# rpihat.net
KiCad netlist of a schematic drawn in EAGLE
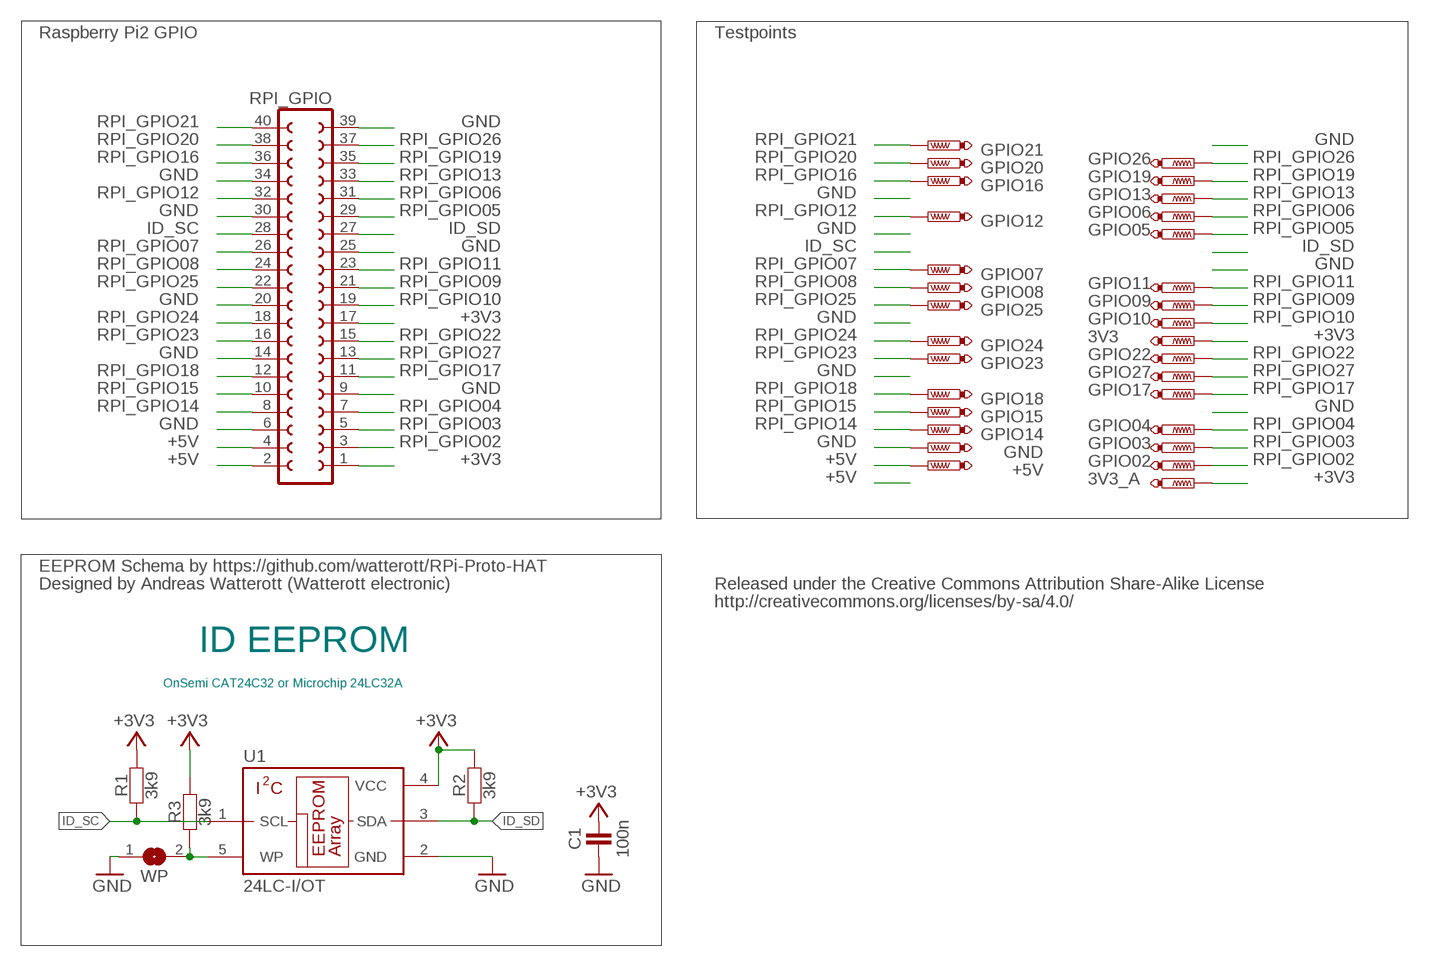
[diagram p0: schematic, sheet 1]

(export (version "E")
  (design (tool "Eeschema 10.0.6"))
  (components
    (comp (ref "+5V")
      (value "PTR1TP06R")
      (footprint "eagle-import:TP06R")
      (libsource (lib "eagle-import") (part "PTR1TP06R"))
    )
    (comp (ref "3V3")
      (value "+3.3V")
      (footprint "eagle-import:TP06R")
      (libsource (lib "eagle-import") (part "PTR1TP06R"))
    )
    (comp (ref "3V3_A")
      (value "+3.3V")
      (footprint "eagle-import:TP06R")
      (libsource (lib "eagle-import") (part "PTR1TP06R"))
    )
    (comp (ref "C1")
      (value "100n")
      (footprint "eagle-import:R0603")
      (libsource (lib "eagle-import") (part "CAPACITOR-C0603"))
    )
    (comp (ref "GND")
      (value "PTR1TP06R")
      (footprint "eagle-import:TP06R")
      (libsource (lib "eagle-import") (part "PTR1TP06R"))
    )
    (comp (ref "GPIO02")
      (value "PTR1TP06R")
      (footprint "eagle-import:TP06R")
      (libsource (lib "eagle-import") (part "PTR1TP06R"))
    )
    (comp (ref "GPIO03")
      (value "PTR1TP06R")
      (footprint "eagle-import:TP06R")
      (libsource (lib "eagle-import") (part "PTR1TP06R"))
    )
    (comp (ref "GPIO04")
      (value "PTR1TP06R")
      (footprint "eagle-import:TP06R")
      (libsource (lib "eagle-import") (part "PTR1TP06R"))
    )
    (comp (ref "GPIO05")
      (value "PTR1TP06R")
      (footprint "eagle-import:TP06R")
      (libsource (lib "eagle-import") (part "PTR1TP06R"))
    )
    (comp (ref "GPIO06")
      (value "PTR1TP06R")
      (footprint "eagle-import:TP06R")
      (libsource (lib "eagle-import") (part "PTR1TP06R"))
    )
    (comp (ref "GPIO07")
      (value "PTR1TP06R")
      (footprint "eagle-import:TP06R")
      (libsource (lib "eagle-import") (part "PTR1TP06R"))
    )
    (comp (ref "GPIO08")
      (value "PTR1TP06R")
      (footprint "eagle-import:TP06R")
      (libsource (lib "eagle-import") (part "PTR1TP06R"))
    )
    (comp (ref "GPIO09")
      (value "PTR1TP06R")
      (footprint "eagle-import:TP06R")
      (libsource (lib "eagle-import") (part "PTR1TP06R"))
    )
    (comp (ref "GPIO10")
      (value "PTR1TP06R")
      (footprint "eagle-import:TP06R")
      (libsource (lib "eagle-import") (part "PTR1TP06R"))
    )
    (comp (ref "GPIO11")
      (value "PTR1TP06R")
      (footprint "eagle-import:TP06R")
      (libsource (lib "eagle-import") (part "PTR1TP06R"))
    )
    (comp (ref "GPIO12")
      (value "PTR1TP06R")
      (footprint "eagle-import:TP06R")
      (libsource (lib "eagle-import") (part "PTR1TP06R"))
    )
    (comp (ref "GPIO13")
      (value "PTR1TP06R")
      (footprint "eagle-import:TP06R")
      (libsource (lib "eagle-import") (part "PTR1TP06R"))
    )
    (comp (ref "GPIO14")
      (value "PTR1TP06R")
      (footprint "eagle-import:TP06R")
      (libsource (lib "eagle-import") (part "PTR1TP06R"))
    )
    (comp (ref "GPIO15")
      (value "PTR1TP06R")
      (footprint "eagle-import:TP06R")
      (libsource (lib "eagle-import") (part "PTR1TP06R"))
    )
    (comp (ref "GPIO16")
      (value "PTR1TP06R")
      (footprint "eagle-import:TP06R")
      (libsource (lib "eagle-import") (part "PTR1TP06R"))
    )
    (comp (ref "GPIO17")
      (value "PTR1TP06R")
      (footprint "eagle-import:TP06R")
      (libsource (lib "eagle-import") (part "PTR1TP06R"))
    )
    (comp (ref "GPIO18")
      (value "PTR1TP06R")
      (footprint "eagle-import:TP06R")
      (libsource (lib "eagle-import") (part "PTR1TP06R"))
    )
    (comp (ref "GPIO19")
      (value "PTR1TP06R")
      (footprint "eagle-import:TP06R")
      (libsource (lib "eagle-import") (part "PTR1TP06R"))
    )
    (comp (ref "GPIO20")
      (value "PTR1TP06R")
      (footprint "eagle-import:TP06R")
      (libsource (lib "eagle-import") (part "PTR1TP06R"))
    )
    (comp (ref "GPIO21")
      (value "PTR1TP06R")
      (footprint "eagle-import:TP06R")
      (libsource (lib "eagle-import") (part "PTR1TP06R"))
    )
    (comp (ref "GPIO22")
      (value "PTR1TP06R")
      (footprint "eagle-import:TP06R")
      (libsource (lib "eagle-import") (part "PTR1TP06R"))
    )
    (comp (ref "GPIO23")
      (value "PTR1TP06R")
      (footprint "eagle-import:TP06R")
      (libsource (lib "eagle-import") (part "PTR1TP06R"))
    )
    (comp (ref "GPIO24")
      (value "PTR1TP06R")
      (footprint "eagle-import:TP06R")
      (libsource (lib "eagle-import") (part "PTR1TP06R"))
    )
    (comp (ref "GPIO25")
      (value "PTR1TP06R")
      (footprint "eagle-import:TP06R")
      (libsource (lib "eagle-import") (part "PTR1TP06R"))
    )
    (comp (ref "GPIO26")
      (value "PTR1TP06R")
      (footprint "eagle-import:TP06R")
      (libsource (lib "eagle-import") (part "PTR1TP06R"))
    )
    (comp (ref "GPIO27")
      (value "PTR1TP06R")
      (footprint "eagle-import:TP06R")
      (libsource (lib "eagle-import") (part "PTR1TP06R"))
    )
    (comp (ref "R1")
      (value "3k9")
      (footprint "eagle-import:R0603")
      (libsource (lib "eagle-import") (part "RESISTOR-R0603"))
    )
    (comp (ref "R2")
      (value "3k9")
      (footprint "eagle-import:R0603")
      (libsource (lib "eagle-import") (part "RESISTOR-R0603"))
    )
    (comp (ref "R3")
      (value "3k9")
      (footprint "eagle-import:R0603")
      (libsource (lib "eagle-import") (part "RESISTOR-R0603"))
    )
    (comp (ref "RPI_GPIO")
      (value "FE20-2")
      (footprint "eagle-import:FE20-2")
      (libsource (lib "eagle-import") (part "FE20-2"))
    )
    (comp (ref "U1")
      (value "24LC-I/OT")
      (footprint "eagle-import:SOT23-5")
      (libsource (lib "eagle-import") (part "24LC-I/OT"))
    )
    (comp (ref "WP")
      (value "JUMPER2-NOCREAM")
      (footprint "eagle-import:JUMPER2_NC")
      (libsource (lib "eagle-import") (part "JUMPER2-NOCREAM"))
    )
  )
  (nets
    (net (code "1") (name "+3V3") (class "Default")
      (node (ref "3V3") (pin "TP") (pinfunction "TP_TP") (pintype "input"))
      (node (ref "3V3_A") (pin "TP") (pinfunction "TP_TP") (pintype "input"))
      (node (ref "C1") (pin "2") (pinfunction "2_2") (pintype "passive"))
      (node (ref "R1") (pin "2") (pinfunction "2_2") (pintype "passive"))
      (node (ref "R2") (pin "2") (pinfunction "2_2") (pintype "passive"))
      (node (ref "R3") (pin "2") (pinfunction "2_2") (pintype "passive"))
      (node (ref "RPI_GPIO") (pin "1") (pinfunction "1_1") (pintype "passive"))
      (node (ref "RPI_GPIO") (pin "17") (pinfunction "17_17") (pintype "passive"))
      (node (ref "U1") (pin "4") (pinfunction "VCC_4") (pintype "power_in"))
    )
    (net (code "2") (name "/+5V") (class "Default")
      (node (ref "+5V") (pin "TP") (pinfunction "TP_TP") (pintype "input"))
      (node (ref "RPI_GPIO") (pin "2") (pinfunction "2_2") (pintype "passive"))
      (node (ref "RPI_GPIO") (pin "4") (pinfunction "4_4") (pintype "passive"))
    )
    (net (code "3") (name "/RPI_GPIO02") (class "Default")
      (node (ref "GPIO02") (pin "TP") (pinfunction "TP_TP") (pintype "input"))
      (node (ref "RPI_GPIO") (pin "3") (pinfunction "3_3") (pintype "passive"))
    )
    (net (code "4") (name "/RPI_GPIO03") (class "Default")
      (node (ref "GPIO03") (pin "TP") (pinfunction "TP_TP") (pintype "input"))
      (node (ref "RPI_GPIO") (pin "5") (pinfunction "5_5") (pintype "passive"))
    )
    (net (code "5") (name "/RPI_GPIO04") (class "Default")
      (node (ref "GPIO04") (pin "TP") (pinfunction "TP_TP") (pintype "input"))
      (node (ref "RPI_GPIO") (pin "7") (pinfunction "7_7") (pintype "passive"))
    )
    (net (code "6") (name "/RPI_GPIO05") (class "Default")
      (node (ref "GPIO05") (pin "TP") (pinfunction "TP_TP") (pintype "input"))
      (node (ref "RPI_GPIO") (pin "29") (pinfunction "29_29") (pintype "passive"))
    )
    (net (code "7") (name "/RPI_GPIO06") (class "Default")
      (node (ref "GPIO06") (pin "TP") (pinfunction "TP_TP") (pintype "input"))
      (node (ref "RPI_GPIO") (pin "31") (pinfunction "31_31") (pintype "passive"))
    )
    (net (code "8") (name "/RPI_GPIO07") (class "Default")
      (node (ref "GPIO07") (pin "TP") (pinfunction "TP_TP") (pintype "input"))
      (node (ref "RPI_GPIO") (pin "26") (pinfunction "26_26") (pintype "passive"))
    )
    (net (code "9") (name "/RPI_GPIO08") (class "Default")
      (node (ref "GPIO08") (pin "TP") (pinfunction "TP_TP") (pintype "input"))
      (node (ref "RPI_GPIO") (pin "24") (pinfunction "24_24") (pintype "passive"))
    )
    (net (code "10") (name "/RPI_GPIO09") (class "Default")
      (node (ref "GPIO09") (pin "TP") (pinfunction "TP_TP") (pintype "input"))
      (node (ref "RPI_GPIO") (pin "21") (pinfunction "21_21") (pintype "passive"))
    )
    (net (code "11") (name "/RPI_GPIO10") (class "Default")
      (node (ref "GPIO10") (pin "TP") (pinfunction "TP_TP") (pintype "input"))
      (node (ref "RPI_GPIO") (pin "19") (pinfunction "19_19") (pintype "passive"))
    )
    (net (code "12") (name "/RPI_GPIO11") (class "Default")
      (node (ref "GPIO11") (pin "TP") (pinfunction "TP_TP") (pintype "input"))
      (node (ref "RPI_GPIO") (pin "23") (pinfunction "23_23") (pintype "passive"))
    )
    (net (code "13") (name "/RPI_GPIO12") (class "Default")
      (node (ref "GPIO12") (pin "TP") (pinfunction "TP_TP") (pintype "input"))
      (node (ref "RPI_GPIO") (pin "32") (pinfunction "32_32") (pintype "passive"))
    )
    (net (code "14") (name "/RPI_GPIO13") (class "Default")
      (node (ref "GPIO13") (pin "TP") (pinfunction "TP_TP") (pintype "input"))
      (node (ref "RPI_GPIO") (pin "33") (pinfunction "33_33") (pintype "passive"))
    )
    (net (code "15") (name "/RPI_GPIO14") (class "Default")
      (node (ref "GPIO14") (pin "TP") (pinfunction "TP_TP") (pintype "input"))
      (node (ref "RPI_GPIO") (pin "8") (pinfunction "8_8") (pintype "passive"))
    )
    (net (code "16") (name "/RPI_GPIO15") (class "Default")
      (node (ref "GPIO15") (pin "TP") (pinfunction "TP_TP") (pintype "input"))
      (node (ref "RPI_GPIO") (pin "10") (pinfunction "10_10") (pintype "passive"))
    )
    (net (code "17") (name "/RPI_GPIO16") (class "Default")
      (node (ref "GPIO16") (pin "TP") (pinfunction "TP_TP") (pintype "input"))
      (node (ref "RPI_GPIO") (pin "36") (pinfunction "36_36") (pintype "passive"))
    )
    (net (code "18") (name "/RPI_GPIO17") (class "Default")
      (node (ref "GPIO17") (pin "TP") (pinfunction "TP_TP") (pintype "input"))
      (node (ref "RPI_GPIO") (pin "11") (pinfunction "11_11") (pintype "passive"))
    )
    (net (code "19") (name "/RPI_GPIO18") (class "Default")
      (node (ref "GPIO18") (pin "TP") (pinfunction "TP_TP") (pintype "input"))
      (node (ref "RPI_GPIO") (pin "12") (pinfunction "12_12") (pintype "passive"))
    )
    (net (code "20") (name "/RPI_GPIO19") (class "Default")
      (node (ref "GPIO19") (pin "TP") (pinfunction "TP_TP") (pintype "input"))
      (node (ref "RPI_GPIO") (pin "35") (pinfunction "35_35") (pintype "passive"))
    )
    (net (code "21") (name "/RPI_GPIO20") (class "Default")
      (node (ref "GPIO20") (pin "TP") (pinfunction "TP_TP") (pintype "input"))
      (node (ref "RPI_GPIO") (pin "38") (pinfunction "38_38") (pintype "passive"))
    )
    (net (code "22") (name "/RPI_GPIO21") (class "Default")
      (node (ref "GPIO21") (pin "TP") (pinfunction "TP_TP") (pintype "input"))
      (node (ref "RPI_GPIO") (pin "40") (pinfunction "40_40") (pintype "passive"))
    )
    (net (code "23") (name "/RPI_GPIO22") (class "Default")
      (node (ref "GPIO22") (pin "TP") (pinfunction "TP_TP") (pintype "input"))
      (node (ref "RPI_GPIO") (pin "15") (pinfunction "15_15") (pintype "passive"))
    )
    (net (code "24") (name "/RPI_GPIO23") (class "Default")
      (node (ref "GPIO23") (pin "TP") (pinfunction "TP_TP") (pintype "input"))
      (node (ref "RPI_GPIO") (pin "16") (pinfunction "16_16") (pintype "passive"))
    )
    (net (code "25") (name "/RPI_GPIO24") (class "Default")
      (node (ref "GPIO24") (pin "TP") (pinfunction "TP_TP") (pintype "input"))
      (node (ref "RPI_GPIO") (pin "18") (pinfunction "18_18") (pintype "passive"))
    )
    (net (code "26") (name "/RPI_GPIO25") (class "Default")
      (node (ref "GPIO25") (pin "TP") (pinfunction "TP_TP") (pintype "input"))
      (node (ref "RPI_GPIO") (pin "22") (pinfunction "22_22") (pintype "passive"))
    )
    (net (code "27") (name "/RPI_GPIO26") (class "Default")
      (node (ref "GPIO26") (pin "TP") (pinfunction "TP_TP") (pintype "input"))
      (node (ref "RPI_GPIO") (pin "37") (pinfunction "37_37") (pintype "passive"))
    )
    (net (code "28") (name "/RPI_GPIO27") (class "Default")
      (node (ref "GPIO27") (pin "TP") (pinfunction "TP_TP") (pintype "input"))
      (node (ref "RPI_GPIO") (pin "13") (pinfunction "13_13") (pintype "passive"))
    )
    (net (code "29") (name "GND") (class "Default")
      (node (ref "C1") (pin "1") (pinfunction "1_1") (pintype "passive"))
      (node (ref "GND") (pin "TP") (pinfunction "TP_TP") (pintype "input"))
      (node (ref "RPI_GPIO") (pin "14") (pinfunction "14_14") (pintype "passive"))
      (node (ref "RPI_GPIO") (pin "20") (pinfunction "20_20") (pintype "passive"))
      (node (ref "RPI_GPIO") (pin "25") (pinfunction "25_25") (pintype "passive"))
      (node (ref "RPI_GPIO") (pin "30") (pinfunction "30_30") (pintype "passive"))
      (node (ref "RPI_GPIO") (pin "34") (pinfunction "34_34") (pintype "passive"))
      (node (ref "RPI_GPIO") (pin "39") (pinfunction "39_39") (pintype "passive"))
      (node (ref "RPI_GPIO") (pin "6") (pinfunction "6_6") (pintype "passive"))
      (node (ref "RPI_GPIO") (pin "9") (pinfunction "9_9") (pintype "passive"))
      (node (ref "U1") (pin "2") (pinfunction "GND_2") (pintype "power_in"))
      (node (ref "WP") (pin "1") (pinfunction "1_1") (pintype "passive"))
    )
    (net (code "30") (name "ID_SC") (class "Default")
      (node (ref "R1") (pin "1") (pinfunction "1_1") (pintype "passive"))
      (node (ref "RPI_GPIO") (pin "28") (pinfunction "28_28") (pintype "passive"))
      (node (ref "U1") (pin "1") (pinfunction "SCL_1") (pintype "bidirectional"))
    )
    (net (code "31") (name "ID_SD") (class "Default")
      (node (ref "R2") (pin "1") (pinfunction "1_1") (pintype "passive"))
      (node (ref "RPI_GPIO") (pin "27") (pinfunction "27_27") (pintype "passive"))
      (node (ref "U1") (pin "3") (pinfunction "SDA_3") (pintype "bidirectional"))
    )
    (net (code "32") (name "Net-(U1-WP)") (class "Default")
      (node (ref "R3") (pin "1") (pinfunction "1_1") (pintype "passive"))
      (node (ref "U1") (pin "5") (pinfunction "WP_5") (pintype "bidirectional"))
      (node (ref "WP") (pin "2") (pinfunction "2_2") (pintype "passive"))
    )
  )
)
